# base.net
KiCad netlist of a schematic drawn in Altium Designer
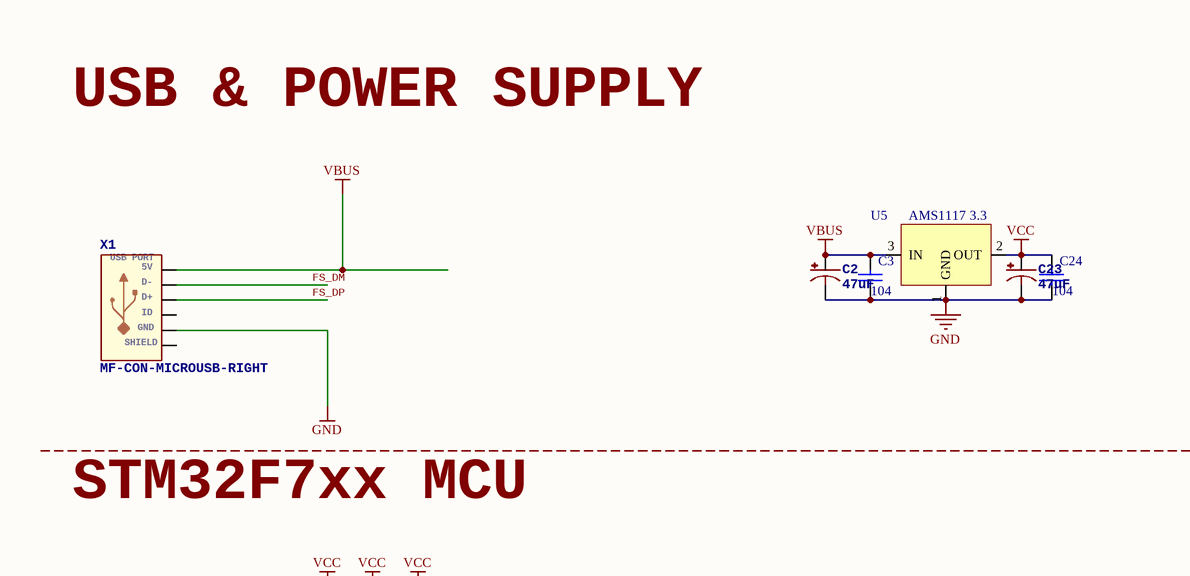
[diagram p0: base.SchDoc, top left]
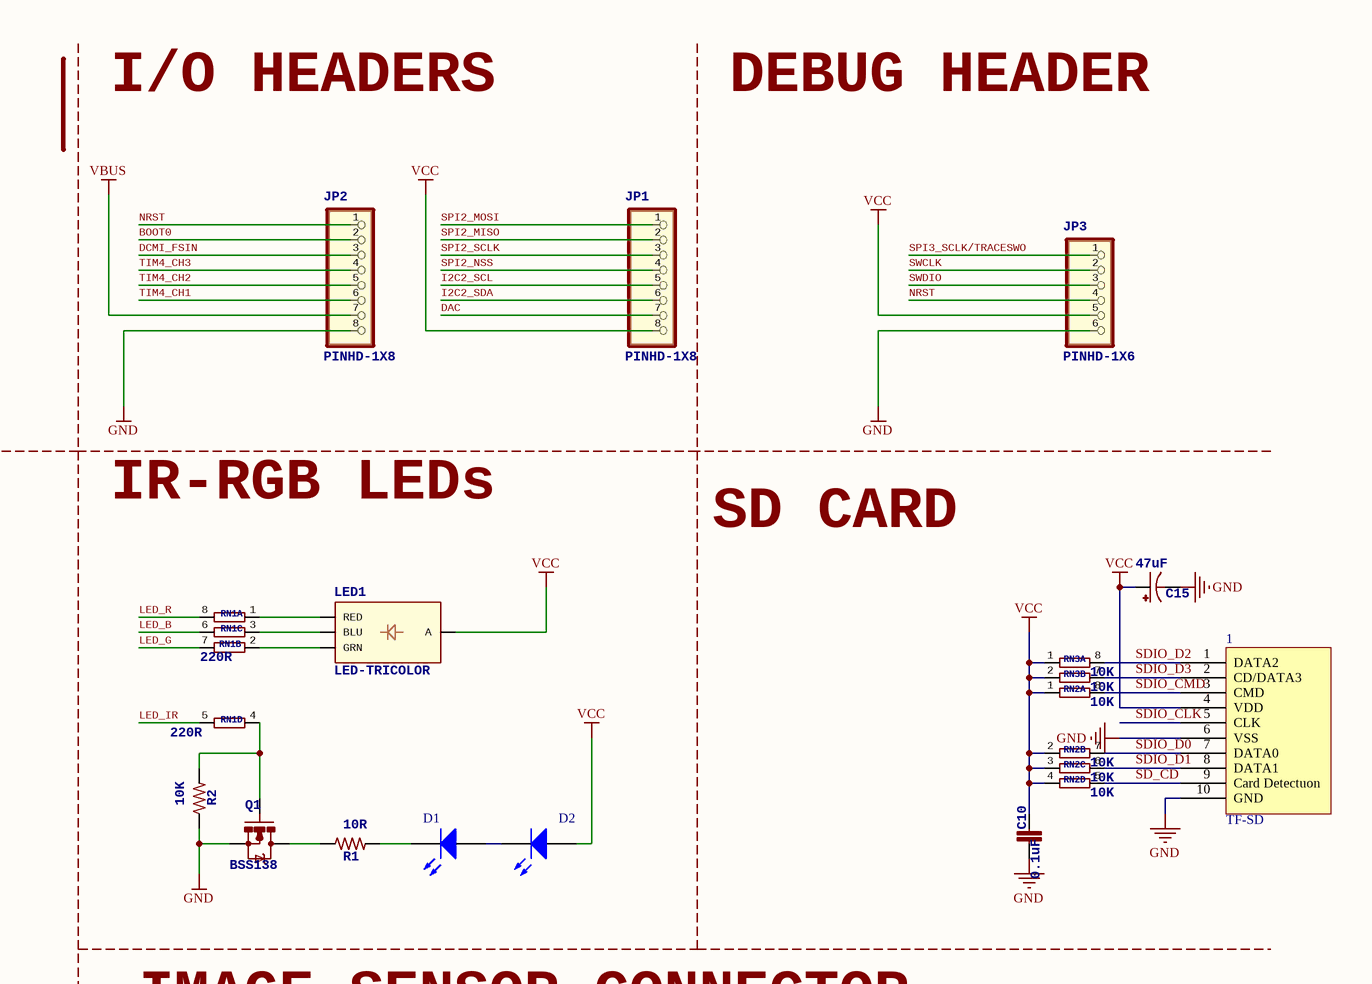
[diagram p1: base.SchDoc, top right]
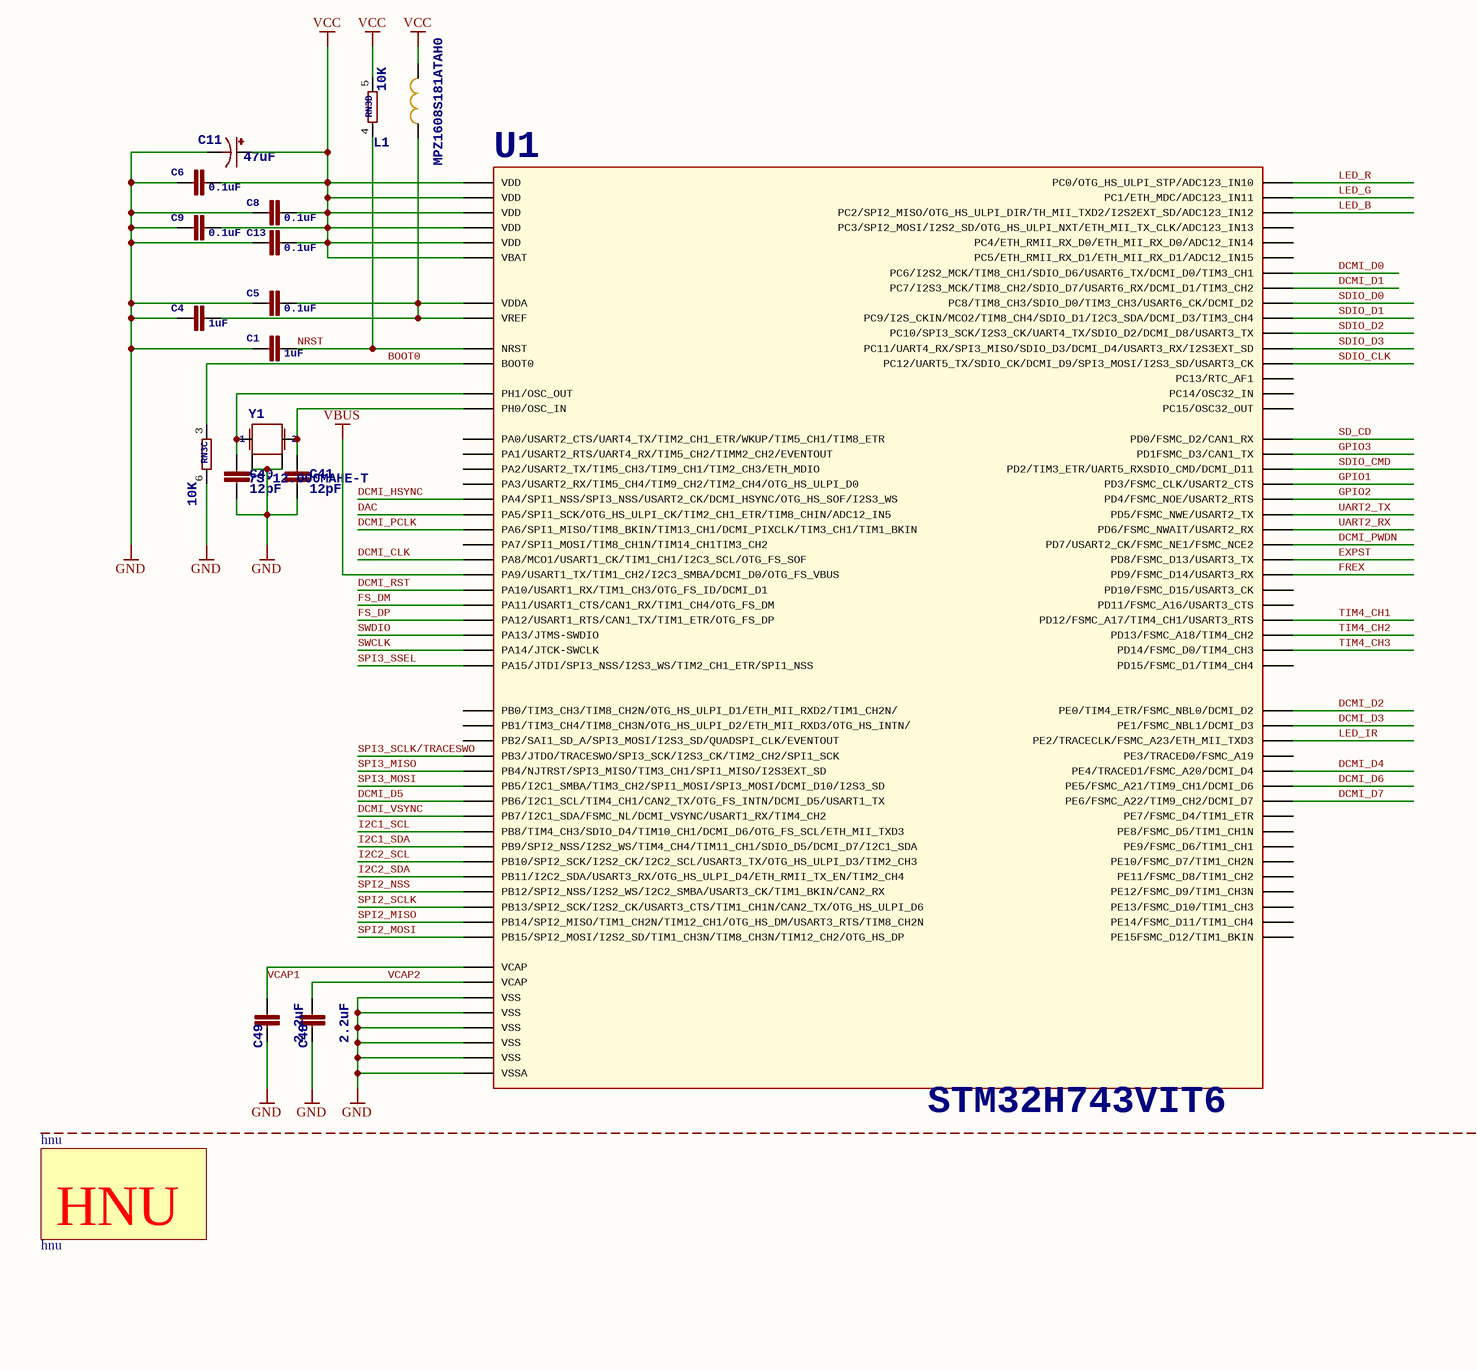
[diagram p2: base.SchDoc, bottom left]
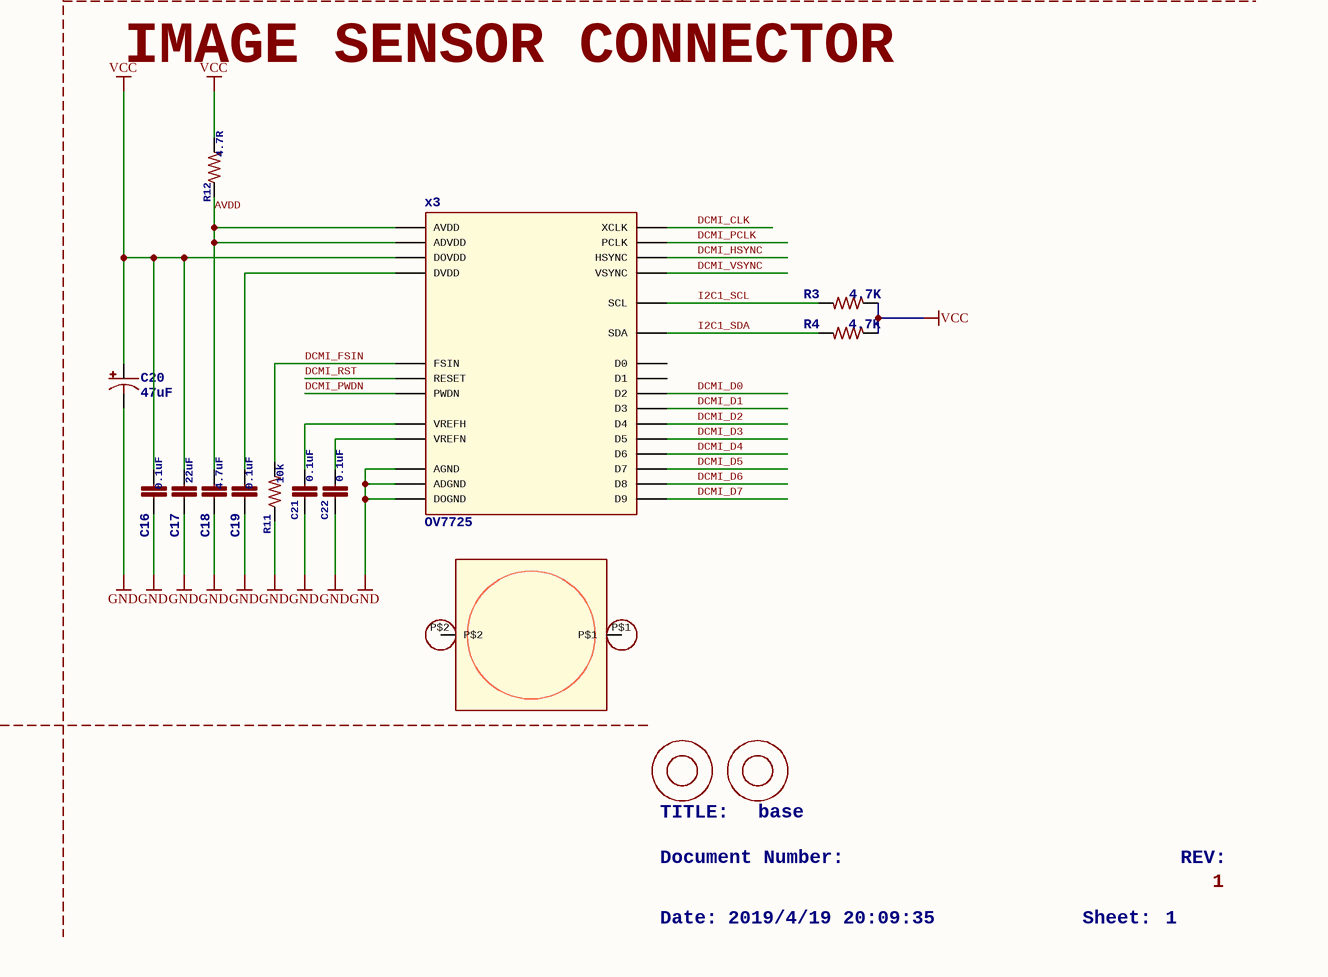
[diagram p3: base.SchDoc, bottom right]

(export (version "E")
  (design (tool "Eeschema 10.0.6"))
  (components
    (comp (ref "1") (value "TF-SD") (footprint "TF") (libsource (lib "base") (part "TF-SD")))
    (comp (ref "C1")
      (value "1uF")
      (footprint "0603-CAP")
      (description "CapacitorStandard 0603 ceramic capacitor, and 0.1\" leaded capacitor.")
      (libsource (lib "") (part "CAP0603-CAP_1"))
    )
    (comp (ref "C2") (value "47uF") (footprint "EIA3216") (libsource (lib "sfe") (part "CAP_POL1206")))
    (comp (ref "C3")
      (value "104")
      (footprint "0603-CAP")
      (description "Capacitor")
      (fields (field (name "Comment") "Cap") (field (name "PUBLISHER") "Altium Limited"))
      (libsource (lib "Miscellaneous Devices") (part "Cap"))
    )
    (comp (ref "C4")
      (value "1uF")
      (footprint "0603-CAP")
      (description "CapacitorStandard 0603 ceramic capacitor, and 0.1\" leaded capacitor.")
      (libsource (lib "") (part "CAP0603-CAP_1"))
    )
    (comp (ref "C5")
      (value "0.1uF")
      (footprint "0603-CAP")
      (description "CapacitorStandard 0603 ceramic capacitor, and 0.1\" leaded capacitor.")
      (libsource (lib "") (part "CAP0603-CAP_1"))
    )
    (comp (ref "C6")
      (value "0.1uF")
      (footprint "0603-CAP")
      (description "CapacitorStandard 0603 ceramic capacitor, and 0.1\" leaded capacitor.")
      (libsource (lib "") (part "CAP0603-CAP_1"))
    )
    (comp (ref "C8")
      (value "0.1uF")
      (footprint "0603-CAP")
      (description "CapacitorStandard 0603 ceramic capacitor, and 0.1\" leaded capacitor.")
      (libsource (lib "") (part "CAP0603-CAP_1"))
    )
    (comp (ref "C9")
      (value "0.1uF")
      (footprint "0603-CAP")
      (description "CapacitorStandard 0603 ceramic capacitor, and 0.1\" leaded capacitor.")
      (libsource (lib "") (part "CAP0603-CAP_1"))
    )
    (comp (ref "C10")
      (value "0.1uF")
      (footprint "0603-CAP")
      (description "CapacitorStandard 0603 ceramic capacitor, and 0.1\" leaded capacitor.")
      (libsource (lib "sfe") (part "CAP0603-CAP"))
    )
    (comp (ref "C11") (value "47uF") (footprint "EIA3216") (libsource (lib "") (part "CAP_POL1206_2")))
    (comp (ref "C13")
      (value "0.1uF")
      (footprint "0603-CAP")
      (description "CapacitorStandard 0603 ceramic capacitor, and 0.1\" leaded capacitor.")
      (libsource (lib "") (part "CAP0603-CAP_1"))
    )
    (comp (ref "C15") (value "47uF") (footprint "EIA3216") (libsource (lib "") (part "CAP_POL1206_1")))
    (comp (ref "C16")
      (value "0.1uF")
      (footprint "0603-CAP")
      (description "CapacitorStandard 0603 ceramic capacitor, and 0.1\" leaded capacitor.")
      (libsource (lib "") (part "CAP0603-CAP_1"))
    )
    (comp (ref "C17")
      (value "22uF")
      (footprint "0603-CAP")
      (description "CapacitorStandard 0603 ceramic capacitor, and 0.1\" leaded capacitor.")
      (libsource (lib "sfe") (part "CAP0805"))
    )
    (comp (ref "C18")
      (value "4.7uF")
      (footprint "0603-CAP")
      (description "CapacitorStandard 0603 ceramic capacitor, and 0.1\" leaded capacitor.")
      (libsource (lib "") (part "CAP0603-CAP_1"))
    )
    (comp (ref "C19")
      (value "0.1uF")
      (footprint "0603-CAP")
      (description "CapacitorStandard 0603 ceramic capacitor, and 0.1\" leaded capacitor.")
      (libsource (lib "") (part "CAP0603-CAP_1"))
    )
    (comp (ref "C20") (value "47uF") (footprint "EIA3216") (libsource (lib "sfe") (part "CAP_POL1206")))
    (comp (ref "C21")
      (value "0.1uF")
      (footprint "0603-CAP")
      (description "CapacitorStandard 0603 ceramic capacitor, and 0.1\" leaded capacitor.")
      (libsource (lib "sfe") (part "CAP0603-CAP"))
    )
    (comp (ref "C22")
      (value "0.1uF")
      (footprint "0603-CAP")
      (description "CapacitorStandard 0603 ceramic capacitor, and 0.1\" leaded capacitor.")
      (libsource (lib "sfe") (part "CAP0603-CAP"))
    )
    (comp (ref "C23") (value "47uF") (footprint "EIA3216") (libsource (lib "sfe") (part "CAP_POL1206")))
    (comp (ref "C24")
      (value "104")
      (footprint "0603-CAP")
      (description "Capacitor")
      (fields (field (name "Comment") "Cap") (field (name "PUBLISHER") "Altium Limited"))
      (libsource (lib "Miscellaneous Devices") (part "Cap"))
    )
    (comp (ref "C40")
      (value "12pF")
      (footprint "0603-CAP")
      (description "CapacitorStandard 0603 ceramic capacitor, and 0.1\" leaded capacitor.")
      (libsource (lib "") (part "CAP0603-CAP_2"))
    )
    (comp (ref "C41")
      (value "12pF")
      (footprint "0603-CAP")
      (description "CapacitorStandard 0603 ceramic capacitor, and 0.1\" leaded capacitor.")
      (libsource (lib "") (part "CAP0603-CAP_2"))
    )
    (comp (ref "C48")
      (value "2.2uF")
      (footprint "0603-CAP")
      (description "CapacitorStandard 0603 ceramic capacitor, and 0.1\" leaded capacitor.")
      (libsource (lib "sfe") (part "CAP0603-CAP"))
    )
    (comp (ref "C49")
      (value "2.2uF")
      (footprint "0603-CAP")
      (description "CapacitorStandard 0603 ceramic capacitor, and 0.1\" leaded capacitor.")
      (libsource (lib "sfe") (part "CAP0603-CAP"))
    )
    (comp (ref "D1")
      (value "LED0")
      (footprint "LED_0603")
      (description "Typical INFRARED GaAs LED")
      (fields (field (name "PUBLISHER") "Altium Limited"))
      (libsource (lib "M4(3333)") (part "LED0"))
    )
    (comp (ref "D2")
      (value "LED0")
      (footprint "LED_0603")
      (description "Typical INFRARED GaAs LED")
      (fields (field (name "PUBLISHER") "Altium Limited"))
      (libsource (lib "M4(3333)") (part "LED0"))
    )
    (comp (ref "hnu") (value "hnu") (footprint "HNU") (libsource (lib "base") (part "hnu")))
    (comp (ref "JP1")
      (value "PINHD-1X8")
      (footprint "1X08")
      (description "PIN HEADER")
      (libsource (lib "base") (part "PINHD-1X8"))
    )
    (comp (ref "JP2")
      (value "PINHD-1X8")
      (footprint "1X08")
      (description "PIN HEADER")
      (libsource (lib "base") (part "PINHD-1X8"))
    )
    (comp (ref "JP3")
      (value "PINHD-1X6")
      (footprint "1X06")
      (description "PIN HEADER")
      (libsource (lib "base") (part "PINHD-1X6"))
    )
    (comp (ref "L1")
      (value "MPZ1608S181ATAH0")
      (footprint "0603")
      (libsource (lib "base") (part "INDUCTOR0603"))
    )
    (comp (ref "LED1")
      (value "LED-TRICOLOR")
      (footprint "rgb")
      (libsource (lib "base") (part "LED-TRICOLOR"))
    )
    (comp (ref "LM1")
      (value "LENSMOUNT20MM")
      (footprint "LENSMOUNT-20MM")
      (libsource (lib "base") (part "LENSMOUNT20MM"))
    )
    (comp (ref "M1")
      (value "9774030243R")
      (footprint "2,8-PAD")
      (libsource (lib "STANDOFFS") (part "9774030151R"))
    )
    (comp (ref "M2")
      (value "9774030243R")
      (footprint "2,8-PAD")
      (libsource (lib "STANDOFFS") (part "9774030151R"))
    )
    (comp (ref "Q1")
      (value "BSS138")
      (footprint "SOT23-3")
      (libsource (lib "sfe") (part "MOSFET-NCHANNELSMD"))
    )
    (comp (ref "R1")
      (value "10R")
      (footprint "0603-RES")
      (description "ResistorBasic schematic elements and footprints for 0603, 1206, and PTH resistors.")
      (libsource (lib "sfe") (part "RESISTOR0603-RES"))
    )
    (comp (ref "R2")
      (value "10K")
      (footprint "0603-RES")
      (description "ResistorBasic schematic elements and footprints for 0603, 1206, and PTH resistors.")
      (libsource (lib "sfe") (part "RESISTOR0603-RES"))
    )
    (comp (ref "R3")
      (value "4.7K")
      (footprint "0603-RES")
      (description "ResistorBasic schematic elements and footprints for 0603, 1206, and PTH resistors.")
      (libsource (lib "sfe") (part "RESISTOR0603-RES"))
    )
    (comp (ref "R4")
      (value "4.7K")
      (footprint "0603-RES")
      (description "ResistorBasic schematic elements and footprints for 0603, 1206, and PTH resistors.")
      (libsource (lib "sfe") (part "RESISTOR0603-RES"))
    )
    (comp (ref "R11")
      (value "10k")
      (footprint "0603-RES")
      (description "ResistorBasic schematic elements and footprints for 0603, 1206, and PTH resistors.")
      (libsource (lib "sfe") (part "RESISTOR0603-RES"))
    )
    (comp (ref "R12")
      (value "4.7R")
      (footprint "0603-RES")
      (description "ResistorBasic schematic elements and footprints for 0603, 1206, and PTH resistors.")
      (libsource (lib "sfe") (part "RESISTOR0603-RES"))
    )
    (comp (ref "RN1")
      (value "220R")
      (footprint "EXBV8V")
      (description "Array Chip Resistor   Source: RS Component / Phycomp")
      (libsource (lib "resistor-dil") (part "4R-NEXBV8V"))
    )
    (comp (ref "RN2")
      (value "10K")
      (footprint "EXBV8V")
      (description "Array Chip Resistor   Source: RS Component / Phycomp")
      (libsource (lib "resistor-dil") (part "4R-NEXBV8V"))
    )
    (comp (ref "RN3")
      (value "10K")
      (footprint "EXBV8V")
      (description "Array Chip Resistor   Source: RS Component / Phycomp")
      (libsource (lib "resistor-dil") (part "4R-NEXBV8V"))
    )
    (comp (ref "U1")
      (value "STM32H743VIT6")
      (footprint "LQFP100")
      (libsource (lib "base") (part "STM32F746LQFP100"))
    )
    (comp (ref "U5") (value "AMS1117 3.3") (footprint "SOT_223") (libsource (lib "主控板载芯片") (part "AMS1117")))
    (comp (ref "X1")
      (value "MF-CON-MICROUSB-RIGHT")
      (footprint "micro_usb")
      (fields
        (field (name "USBPORT") "USB PORT")
        (field (name "5V") "5V")
        (field (name "D-") "D-")
        (field (name "D+") "D+")
        (field (name "ID") "ID")
        (field (name "GND") "GND")
        (field (name "SHIELD") "SHIELD")
      )
      (libsource (lib "base") (part "USB_MICRO_RIGHT"))
    )
    (comp (ref "x3") (value "OV7725") (footprint "CSP2-28") (libsource (lib "base") (part "OV7725")))
    (comp (ref "Y1")
      (value "7S-12.000MAHE-T")
      (footprint "CRYSTAL-2.5X2.0")
      (description "CrystalsVarious standard crystals. Proven footprints. Spark Fun Electronics SKU : COM-00534")
      (fields (field (name "1") "1") (field (name "2") "2"))
      (libsource (lib "mux") (part "CRYSTAL2.5X2.0"))
    )
  )
  (nets
    (net (code "1") (name "/AVDD") (class "Default")
      (node (ref "C18") (pin "1") (pinfunction "1_1") (pintype "passive"))
      (node (ref "R12") (pin "1") (pinfunction "1_1") (pintype "passive"))
      (node (ref "x3") (pin "A1") (pinfunction "ADVDD_A1") (pintype "power_in"))
      (node (ref "x3") (pin "B3") (pinfunction "AVDD_B3") (pintype "power_in"))
    )
    (net (code "2") (name "/BOOT0") (class "Default")
      (node (ref "JP2") (pin "2") (pinfunction "2_2") (pintype "passive"))
      (node (ref "RN3") (pin "3") (pinfunction "1_3") (pintype "passive"))
      (node (ref "U1") (pin "94") (pinfunction "BOOT0_94") (pintype "passive"))
    )
    (net (code "3") (name "/DAC") (class "Default")
      (node (ref "JP1") (pin "7") (pinfunction "7_7") (pintype "passive"))
      (node (ref "U1") (pin "29") (pinfunction "PA5/SPI1_SCK/OTG_HS_ULPI_CK/TIM2_CH1_ETR/TIM8_CHIN/ADC12_IN5_29") (pintype "passive"))
    )
    (net (code "4") (name "/DCMI_CLK") (class "Default")
      (node (ref "U1") (pin "67") (pinfunction "PA8/MCO1/USART1_CK/TIM1_CH1/I2C3_SCL/OTG_FS_SOF_67") (pintype "passive"))
      (node (ref "x3") (pin "F3") (pinfunction "XCLK_F3") (pintype "passive"))
    )
    (net (code "5") (name "/DCMI_D0") (class "Default")
      (node (ref "U1") (pin "63") (pinfunction "PC6/I2S2_MCK/TIM8_CH1/SDIO_D6/USART6_TX/DCMI_D0/TIM3_CH1_63") (pintype "passive"))
      (node (ref "x3") (pin "F5") (pinfunction "D2_F5") (pintype "passive"))
    )
    (net (code "6") (name "/DCMI_D1") (class "Default")
      (node (ref "U1") (pin "64") (pinfunction "PC7/I2S3_MCK/TIM8_CH2/SDIO_D7/USART6_RX/DCMI_D1/TIM3_CH2_64") (pintype "passive"))
      (node (ref "x3") (pin "F2") (pinfunction "D3_F2") (pintype "passive"))
    )
    (net (code "7") (name "/DCMI_D2") (class "Default")
      (node (ref "U1") (pin "97") (pinfunction "PE0/TIM4_ETR/FSMC_NBL0/DCMI_D2_97") (pintype "passive"))
      (node (ref "x3") (pin "D6") (pinfunction "D4_D6") (pintype "passive"))
    )
    (net (code "8") (name "/DCMI_D3") (class "Default")
      (node (ref "U1") (pin "98") (pinfunction "PE1/FSMC_NBL1/DCMI_D3_98") (pintype "passive"))
      (node (ref "x3") (pin "D1") (pinfunction "D5_D1") (pintype "passive"))
    )
    (net (code "9") (name "/DCMI_D4") (class "Default")
      (node (ref "U1") (pin "3") (pinfunction "PE4/TRACED1/FSMC_A20/DCMI_D4_3") (pintype "passive"))
      (node (ref "x3") (pin "E6") (pinfunction "D6_E6") (pintype "passive"))
    )
    (net (code "10") (name "/DCMI_D5") (class "Default")
      (node (ref "U1") (pin "92") (pinfunction "PB6/I2C1_SCL/TIM4_CH1/CAN2_TX/OTG_FS_INTN/DCMI_D5/USART1_TX_92") (pintype "passive"))
      (node (ref "x3") (pin "E1") (pinfunction "D7_E1") (pintype "passive"))
    )
    (net (code "11") (name "/DCMI_D6") (class "Default")
      (node (ref "U1") (pin "4") (pinfunction "PE5/FSMC_A21/TIM9_CH1/DCMI_D6_4") (pintype "passive"))
      (node (ref "x3") (pin "F6") (pinfunction "D8_F6") (pintype "passive"))
    )
    (net (code "12") (name "/DCMI_D7") (class "Default")
      (node (ref "U1") (pin "5") (pinfunction "PE6/FSMC_A22/TIM9_CH2/DCMI_D7_5") (pintype "passive"))
      (node (ref "x3") (pin "F1") (pinfunction "D9_F1") (pintype "passive"))
    )
    (net (code "13") (name "/DCMI_FSIN") (class "Default")
      (node (ref "JP2") (pin "3") (pinfunction "3_3") (pintype "passive"))
      (node (ref "R11") (pin "2") (pinfunction "2_2") (pintype "passive"))
      (node (ref "x3") (pin "A4") (pinfunction "FSIN_A4") (pintype "passive"))
    )
    (net (code "14") (name "/DCMI_HSYNC") (class "Default")
      (node (ref "U1") (pin "28") (pinfunction "PA4/SPI1_NSS/SPI3_NSS/USART2_CK/DCMI_HSYNC/OTG_HS_SOF/I2S3_WS_28") (pintype "passive"))
      (node (ref "x3") (pin "B6") (pinfunction "HSYNC_B6") (pintype "passive"))
    )
    (net (code "15") (name "/DCMI_PCLK") (class "Default")
      (node (ref "U1") (pin "30") (pinfunction "PA6/SPI1_MISO/TIM8_BKIN/TIM13_CH1/DCMI_PIXCLK/TIM3_CH1/TIM1_BKIN_30") (pintype "passive"))
      (node (ref "x3") (pin "E4") (pinfunction "PCLK_E4") (pintype "passive"))
    )
    (net (code "16") (name "/DCMI_PWDN") (class "Default")
      (node (ref "U1") (pin "88") (pinfunction "PD7/USART2_CK/FSMC_NE1/FSMC_NCE2_88") (pintype "passive"))
      (node (ref "x3") (pin "C1") (pinfunction "PWDN_C1") (pintype "passive"))
    )
    (net (code "17") (name "/DCMI_RST") (class "Default")
      (node (ref "U1") (pin "69") (pinfunction "PA10/USART1_RX/TIM1_CH3/OTG_FS_ID/DCMI_D1_69") (pintype "passive"))
      (node (ref "x3") (pin "A2") (pinfunction "RESET_A2") (pintype "passive"))
    )
    (net (code "18") (name "/DCMI_VSYNC") (class "Default")
      (node (ref "U1") (pin "93") (pinfunction "PB7/I2C1_SDA/FSMC_NL/DCMI_VSYNC/USART1_RX/TIM4_CH2_93") (pintype "passive"))
      (node (ref "x3") (pin "C6") (pinfunction "VSYNC_C6") (pintype "passive"))
    )
    (net (code "19") (name "/EXPST") (class "Default")
      (node (ref "U1") (pin "55") (pinfunction "PD8/FSMC_D13/USART3_TX_55") (pintype "passive"))
    )
    (net (code "20") (name "/FREX") (class "Default")
      (node (ref "U1") (pin "56") (pinfunction "PD9/FSMC_D14/USART3_RX_56") (pintype "passive"))
    )
    (net (code "21") (name "/FS_DM") (class "Default")
      (node (ref "U1") (pin "70") (pinfunction "PA11/USART1_CTS/CAN1_RX/TIM1_CH4/OTG_FS_DM_70") (pintype "passive"))
      (node (ref "X1") (pin "2") (pinfunction "D-_2") (pintype "passive"))
    )
    (net (code "22") (name "/FS_DP") (class "Default")
      (node (ref "U1") (pin "71") (pinfunction "PA12/USART1_RTS/CAN1_TX/TIM1_ETR/OTG_FS_DP_71") (pintype "passive"))
      (node (ref "X1") (pin "3") (pinfunction "D+_3") (pintype "passive"))
    )
    (net (code "23") (name "/GPIO1") (class "Default")
      (node (ref "U1") (pin "84") (pinfunction "PD3/FSMC_CLK/USART2_CTS_84") (pintype "passive"))
    )
    (net (code "24") (name "/GPIO2") (class "Default")
      (node (ref "U1") (pin "85") (pinfunction "PD4/FSMC_NOE/USART2_RTS_85") (pintype "passive"))
    )
    (net (code "25") (name "/GPIO3") (class "Default")
      (node (ref "U1") (pin "82") (pinfunction "PD1FSMC_D3/CAN1_TX_82") (pintype "passive"))
    )
    (net (code "26") (name "/I2C1_SCL") (class "Default")
      (node (ref "R3") (pin "2") (pinfunction "2_2") (pintype "passive"))
      (node (ref "U1") (pin "95") (pinfunction "PB8/TIM4_CH3/SDIO_D4/TIM10_CH1/DCMI_D6/OTG_FS_SCL/ETH_MII_TXD3_95") (pintype "passive"))
      (node (ref "x3") (pin "A5") (pinfunction "SCL_A5") (pintype "passive"))
    )
    (net (code "27") (name "/I2C1_SDA") (class "Default")
      (node (ref "R4") (pin "2") (pinfunction "2_2") (pintype "passive"))
      (node (ref "U1") (pin "96") (pinfunction "PB9/SPI2_NSS/I2S2_WS/TIM4_CH4/TIM11_CH1/SDIO_D5/DCMI_D7/I2C1_SDA_96") (pintype "passive"))
      (node (ref "x3") (pin "B5") (pinfunction "SDA_B5") (pintype "passive"))
    )
    (net (code "28") (name "/I2C2_SCL") (class "Default")
      (node (ref "JP1") (pin "5") (pinfunction "5_5") (pintype "passive"))
      (node (ref "U1") (pin "46") (pinfunction "PB10/SPI2_SCK/I2S2_CK/I2C2_SCL/USART3_TX/OTG_HS_ULPI_D3/TIM2_CH3_46") (pintype "passive"))
    )
    (net (code "29") (name "/I2C2_SDA") (class "Default")
      (node (ref "JP1") (pin "6") (pinfunction "6_6") (pintype "passive"))
      (node (ref "U1") (pin "47") (pinfunction "PB11/I2C2_SDA/USART3_RX/OTG_HS_ULPI_D4/ETH_RMII_TX_EN/TIM2_CH4_47") (pintype "passive"))
    )
    (net (code "30") (name "/LED_B") (class "Default")
      (node (ref "RN1") (pin "6") (pinfunction "2_6") (pintype "passive"))
      (node (ref "U1") (pin "17") (pinfunction "PC2/SPI2_MISO/OTG_HS_ULPI_DIR/TH_MII_TXD2/I2S2EXT_SD/ADC123_IN12_17") (pintype "passive"))
    )
    (net (code "31") (name "/LED_G") (class "Default")
      (node (ref "RN1") (pin "7") (pinfunction "2_7") (pintype "passive"))
      (node (ref "U1") (pin "16") (pinfunction "PC1/ETH_MDC/ADC123_IN11_16") (pintype "passive"))
    )
    (net (code "32") (name "/LED_IR") (class "Default")
      (node (ref "RN1") (pin "5") (pinfunction "2_5") (pintype "passive"))
      (node (ref "U1") (pin "1") (pinfunction "PE2/TRACECLK/FSMC_A23/ETH_MII_TXD3_1") (pintype "passive"))
    )
    (net (code "33") (name "/LED_R") (class "Default")
      (node (ref "RN1") (pin "8") (pinfunction "2_8") (pintype "passive"))
      (node (ref "U1") (pin "15") (pinfunction "PC0/OTG_HS_ULPI_STP/ADC123_IN10_15") (pintype "passive"))
    )
    (net (code "34") (name "/NRST") (class "Default")
      (node (ref "C1") (pin "1") (pinfunction "1_1") (pintype "passive"))
      (node (ref "JP2") (pin "1") (pinfunction "1_1") (pintype "passive"))
      (node (ref "JP3") (pin "4") (pinfunction "4_4") (pintype "passive"))
      (node (ref "RN3") (pin "4") (pinfunction "1_4") (pintype "passive"))
      (node (ref "U1") (pin "14") (pinfunction "NRST_14") (pintype "passive"))
    )
    (net (code "35") (name "/SDIO_CLK") (class "Default")
      (node (ref "1") (pin "5") (pinfunction "CLK_5") (pintype "passive"))
      (node (ref "U1") (pin "80") (pinfunction "PC12/UART5_TX/SDIO_CK/DCMI_D9/SPI3_MOSI/I2S3_SD/USART3_CK_80") (pintype "passive"))
    )
    (net (code "36") (name "/SDIO_CMD") (class "Default")
      (node (ref "1") (pin "3") (pinfunction "CMD_3") (pintype "passive"))
      (node (ref "RN2") (pin "8") (pinfunction "2_8") (pintype "passive"))
      (node (ref "U1") (pin "83") (pinfunction "PD2/TIM3_ETR/UART5_RXSDIO_CMD/DCMI_D11_83") (pintype "passive"))
    )
    (net (code "37") (name "/SDIO_D0") (class "Default")
      (node (ref "1") (pin "7") (pinfunction "DATA0_7") (pintype "passive"))
      (node (ref "RN2") (pin "7") (pinfunction "2_7") (pintype "passive"))
      (node (ref "U1") (pin "65") (pinfunction "PC8/TIM8_CH3/SDIO_D0/TIM3_CH3/USART6_CK/DCMI_D2_65") (pintype "passive"))
    )
    (net (code "38") (name "/SDIO_D1") (class "Default")
      (node (ref "1") (pin "8") (pinfunction "DATA1_8") (pintype "passive"))
      (node (ref "RN2") (pin "6") (pinfunction "2_6") (pintype "passive"))
      (node (ref "U1") (pin "66") (pinfunction "PC9/I2S_CKIN/MCO2/TIM8_CH4/SDIO_D1/I2C3_SDA/DCMI_D3/TIM3_CH4_66") (pintype "passive"))
    )
    (net (code "39") (name "/SDIO_D2") (class "Default")
      (node (ref "1") (pin "1") (pinfunction "DATA2_1") (pintype "passive"))
      (node (ref "RN3") (pin "8") (pinfunction "2_8") (pintype "passive"))
      (node (ref "U1") (pin "78") (pinfunction "PC10/SPI3_SCK/I2S3_CK/UART4_TX/SDIO_D2/DCMI_D8/USART3_TX_78") (pintype "passive"))
    )
    (net (code "40") (name "/SDIO_D3") (class "Default")
      (node (ref "1") (pin "2") (pinfunction "CD/DATA3_2") (pintype "passive"))
      (node (ref "RN3") (pin "7") (pinfunction "2_7") (pintype "passive"))
      (node (ref "U1") (pin "79") (pinfunction "PC11/UART4_RX/SPI3_MISO/SDIO_D3/DCMI_D4/USART3_RX/I2S3EXT_SD_79") (pintype "passive"))
    )
    (net (code "41") (name "/SD_CD") (class "Default")
      (node (ref "1") (pin "9") (pinfunction "Card_Detectuon_9") (pintype "passive"))
      (node (ref "RN2") (pin "5") (pinfunction "2_5") (pintype "passive"))
      (node (ref "U1") (pin "81") (pinfunction "PD0/FSMC_D2/CAN1_RX_81") (pintype "passive"))
    )
    (net (code "42") (name "/SPI2_MISO") (class "Default")
      (node (ref "JP1") (pin "2") (pinfunction "2_2") (pintype "passive"))
      (node (ref "U1") (pin "53") (pinfunction "PB14/SPI2_MISO/TIM1_CH2N/TIM12_CH1/OTG_HS_DM/USART3_RTS/TIM8_CH2N_53") (pintype "passive"))
    )
    (net (code "43") (name "/SPI2_MOSI") (class "Default")
      (node (ref "JP1") (pin "1") (pinfunction "1_1") (pintype "passive"))
      (node (ref "U1") (pin "54") (pinfunction "PB15/SPI2_MOSI/I2S2_SD/TIM1_CH3N/TIM8_CH3N/TIM12_CH2/OTG_HS_DP_54") (pintype "passive"))
    )
    (net (code "44") (name "/SPI2_NSS") (class "Default")
      (node (ref "JP1") (pin "4") (pinfunction "4_4") (pintype "passive"))
      (node (ref "U1") (pin "51") (pinfunction "PB12/SPI2_NSS/I2S2_WS/I2C2_SMBA/USART3_CK/TIM1_BKIN/CAN2_RX_51") (pintype "passive"))
    )
    (net (code "45") (name "/SPI2_SCLK") (class "Default")
      (node (ref "JP1") (pin "3") (pinfunction "3_3") (pintype "passive"))
      (node (ref "U1") (pin "52") (pinfunction "PB13/SPI2_SCK/I2S2_CK/USART3_CTS/TIM1_CH1N/CAN2_TX/OTG_HS_ULPI_D6_52") (pintype "passive"))
    )
    (net (code "46") (name "/SPI3_MISO") (class "Default")
      (node (ref "U1") (pin "90") (pinfunction "PB4/NJTRST/SPI3_MISO/TIM3_CH1/SPI1_MISO/I2S3EXT_SD_90") (pintype "passive"))
    )
    (net (code "47") (name "/SPI3_MOSI") (class "Default")
      (node (ref "U1") (pin "91") (pinfunction "PB5/I2C1_SMBA/TIM3_CH2/SPI1_MOSI/SPI3_MOSI/DCMI_D10/I2S3_SD_91") (pintype "passive"))
    )
    (net (code "48") (name "/SPI3_SCLK{slash}TRACESWO") (class "Default")
      (node (ref "JP3") (pin "1") (pinfunction "1_1") (pintype "passive"))
      (node (ref "U1") (pin "89") (pinfunction "PB3/JTDO/TRACESWO/SPI3_SCK/I2S3_CK/TIM2_CH2/SPI1_SCK_89") (pintype "passive"))
    )
    (net (code "49") (name "/SPI3_SSEL") (class "Default")
      (node (ref "U1") (pin "77") (pinfunction "PA15/JTDI/SPI3_NSS/I2S3_WS/TIM2_CH1_ETR/SPI1_NSS_77") (pintype "passive"))
    )
    (net (code "50") (name "/SWCLK") (class "Default")
      (node (ref "JP3") (pin "2") (pinfunction "2_2") (pintype "passive"))
      (node (ref "U1") (pin "76") (pinfunction "PA14/JTCK-SWCLK_76") (pintype "passive"))
    )
    (net (code "51") (name "/SWDIO") (class "Default")
      (node (ref "JP3") (pin "3") (pinfunction "3_3") (pintype "passive"))
      (node (ref "U1") (pin "72") (pinfunction "PA13/JTMS-SWDIO_72") (pintype "passive"))
    )
    (net (code "52") (name "/TIM4_CH1") (class "Default")
      (node (ref "JP2") (pin "6") (pinfunction "6_6") (pintype "passive"))
      (node (ref "U1") (pin "59") (pinfunction "PD12/FSMC_A17/TIM4_CH1/USART3_RTS_59") (pintype "passive"))
    )
    (net (code "53") (name "/TIM4_CH2") (class "Default")
      (node (ref "JP2") (pin "5") (pinfunction "5_5") (pintype "passive"))
      (node (ref "U1") (pin "60") (pinfunction "PD13/FSMC_A18/TIM4_CH2_60") (pintype "passive"))
    )
    (net (code "54") (name "/TIM4_CH3") (class "Default")
      (node (ref "JP2") (pin "4") (pinfunction "4_4") (pintype "passive"))
      (node (ref "U1") (pin "61") (pinfunction "PD14/FSMC_D0/TIM4_CH3_61") (pintype "passive"))
    )
    (net (code "55") (name "/UART2_RX") (class "Default")
      (node (ref "U1") (pin "87") (pinfunction "PD6/FSMC_NWAIT/USART2_RX_87") (pintype "passive"))
    )
    (net (code "56") (name "/UART2_TX") (class "Default")
      (node (ref "U1") (pin "86") (pinfunction "PD5/FSMC_NWE/USART2_TX_86") (pintype "passive"))
    )
    (net (code "57") (name "/VCAP1") (class "Default")
      (node (ref "C49") (pin "1") (pinfunction "1_1") (pintype "passive"))
      (node (ref "U1") (pin "48") (pinfunction "VCAP_48") (pintype "power_in"))
    )
    (net (code "58") (name "/VCAP2") (class "Default")
      (node (ref "C48") (pin "1") (pinfunction "1_1") (pintype "passive"))
      (node (ref "U1") (pin "73") (pinfunction "VCAP_73") (pintype "power_in"))
    )
    (net (code "59") (name "GND") (class "Default")
      (node (ref "1") (pin "10") (pinfunction "GND_10") (pintype "passive"))
      (node (ref "1") (pin "6") (pinfunction "VSS_6") (pintype "passive"))
      (node (ref "C1") (pin "2") (pinfunction "2_2") (pintype "passive"))
      (node (ref "C10") (pin "2") (pinfunction "2_2") (pintype "passive"))
      (node (ref "C11") (pin "C") (pinfunction "-_C") (pintype "passive"))
      (node (ref "C13") (pin "2") (pinfunction "2_2") (pintype "passive"))
      (node (ref "C15") (pin "C") (pinfunction "-_C") (pintype "passive"))
      (node (ref "C16") (pin "2") (pinfunction "2_2") (pintype "passive"))
      (node (ref "C17") (pin "2") (pinfunction "2_2") (pintype "passive"))
      (node (ref "C18") (pin "2") (pinfunction "2_2") (pintype "passive"))
      (node (ref "C19") (pin "2") (pinfunction "2_2") (pintype "passive"))
      (node (ref "C2") (pin "C") (pinfunction "-_C") (pintype "passive"))
      (node (ref "C20") (pin "C") (pinfunction "-_C") (pintype "passive"))
      (node (ref "C21") (pin "2") (pinfunction "2_2") (pintype "passive"))
      (node (ref "C22") (pin "2") (pinfunction "2_2") (pintype "passive"))
      (node (ref "C23") (pin "C") (pinfunction "-_C") (pintype "passive"))
      (node (ref "C24") (pin "2") (pinfunction "2_2") (pintype "passive"))
      (node (ref "C3") (pin "2") (pinfunction "2_2") (pintype "passive"))
      (node (ref "C4") (pin "2") (pinfunction "2_2") (pintype "passive"))
      (node (ref "C40") (pin "1") (pinfunction "1_1") (pintype "passive"))
      (node (ref "C41") (pin "1") (pinfunction "1_1") (pintype "passive"))
      (node (ref "C48") (pin "2") (pinfunction "2_2") (pintype "passive"))
      (node (ref "C49") (pin "2") (pinfunction "2_2") (pintype "passive"))
      (node (ref "C5") (pin "2") (pinfunction "2_2") (pintype "passive"))
      (node (ref "C6") (pin "2") (pinfunction "2_2") (pintype "passive"))
      (node (ref "C8") (pin "2") (pinfunction "2_2") (pintype "passive"))
      (node (ref "C9") (pin "2") (pinfunction "2_2") (pintype "passive"))
      (node (ref "JP2") (pin "8") (pinfunction "8_8") (pintype "passive"))
      (node (ref "JP3") (pin "6") (pinfunction "6_6") (pintype "passive"))
      (node (ref "Q1") (pin "2") (pinfunction "S_2") (pintype "passive"))
      (node (ref "R11") (pin "1") (pinfunction "1_1") (pintype "passive"))
      (node (ref "R2") (pin "1") (pinfunction "1_1") (pintype "passive"))
      (node (ref "RN3") (pin "6") (pinfunction "2_6") (pintype "passive"))
      (node (ref "U1") (pin "10") (pinfunction "VSS_10") (pintype "power_in"))
      (node (ref "U1") (pin "19") (pinfunction "VSSA_19") (pintype "power_in"))
      (node (ref "U1") (pin "26") (pinfunction "VSS_26") (pintype "power_in"))
      (node (ref "U1") (pin "49") (pinfunction "VSS_49") (pintype "power_in"))
      (node (ref "U1") (pin "74") (pinfunction "VSS_74") (pintype "power_in"))
      (node (ref "U1") (pin "99") (pinfunction "VSS_99") (pintype "power_in"))
      (node (ref "U5") (pin "1") (pinfunction "GND_1") (pintype "passive"))
      (node (ref "X1") (pin "5") (pinfunction "GND_5") (pintype "power_in"))
      (node (ref "Y1") (pin "2") (pinfunction "P$1_2") (pintype "open_emitter"))
      (node (ref "Y1") (pin "4") (pinfunction "P$2_4") (pintype "open_emitter"))
      (node (ref "x3") (pin "B1") (pinfunction "ADGND_B1") (pintype "power_in"))
      (node (ref "x3") (pin "B4") (pinfunction "AGND_B4") (pintype "power_in"))
      (node (ref "x3") (pin "F4") (pinfunction "DOGND_F4") (pintype "power_in"))
    )
    (net (code "60") (name "Net-(D1-A)") (class "Default")
      (node (ref "D1") (pin "1") (pinfunction "A_1") (pintype "passive"))
      (node (ref "D2") (pin "2") (pinfunction "K_2") (pintype "passive"))
    )
    (net (code "61") (name "Net-(D1-K)") (class "Default")
      (node (ref "D1") (pin "2") (pinfunction "K_2") (pintype "passive"))
      (node (ref "R1") (pin "2") (pinfunction "2_2") (pintype "passive"))
    )
    (net (code "62") (name "Net-(LED1-BLU)") (class "Default")
      (node (ref "LED1") (pin "B") (pinfunction "BLU_B") (pintype "passive"))
      (node (ref "RN1") (pin "3") (pinfunction "1_3") (pintype "passive"))
    )
    (net (code "63") (name "Net-(LED1-GRN)") (class "Default")
      (node (ref "LED1") (pin "G") (pinfunction "GRN_G") (pintype "passive"))
      (node (ref "RN1") (pin "2") (pinfunction "1_2") (pintype "passive"))
    )
    (net (code "64") (name "Net-(LED1-RED)") (class "Default")
      (node (ref "LED1") (pin "R") (pinfunction "RED_R") (pintype "passive"))
      (node (ref "RN1") (pin "1") (pinfunction "1_1") (pintype "passive"))
    )
    (net (code "65") (name "Net-(Q1-D)") (class "Default")
      (node (ref "Q1") (pin "3") (pinfunction "D_3") (pintype "passive"))
      (node (ref "R1") (pin "1") (pinfunction "1_1") (pintype "passive"))
    )
    (net (code "66") (name "Net-(Q1-G)") (class "Default")
      (node (ref "Q1") (pin "1") (pinfunction "G_1") (pintype "passive"))
      (node (ref "R2") (pin "2") (pinfunction "2_2") (pintype "passive"))
      (node (ref "RN1") (pin "4") (pinfunction "1_4") (pintype "passive"))
    )
    (net (code "67") (name "Net-(U1-PH0{slash}OSC_IN)") (class "Default")
      (node (ref "C41") (pin "2") (pinfunction "2_2") (pintype "passive"))
      (node (ref "U1") (pin "12") (pinfunction "PH0/OSC_IN_12") (pintype "passive"))
      (node (ref "Y1") (pin "1") (pinfunction "1_1") (pintype "passive"))
    )
    (net (code "68") (name "Net-(U1-PH1{slash}OSC_OUT)") (class "Default")
      (node (ref "C40") (pin "2") (pinfunction "2_2") (pintype "passive"))
      (node (ref "U1") (pin "13") (pinfunction "PH1/OSC_OUT_13") (pintype "passive"))
      (node (ref "Y1") (pin "3") (pinfunction "2_3") (pintype "passive"))
    )
    (net (code "69") (name "Net-(U1-VDDA)") (class "Default")
      (node (ref "C4") (pin "1") (pinfunction "1_1") (pintype "passive"))
      (node (ref "C5") (pin "1") (pinfunction "1_1") (pintype "passive"))
      (node (ref "L1") (pin "1") (pinfunction "1_1") (pintype "passive"))
      (node (ref "U1") (pin "20") (pinfunction "VREF_20") (pintype "power_in"))
      (node (ref "U1") (pin "21") (pinfunction "VDDA_21") (pintype "power_in"))
    )
    (net (code "70") (name "Net-(x3-DVDD)") (class "Default")
      (node (ref "C19") (pin "1") (pinfunction "1_1") (pintype "passive"))
      (node (ref "x3") (pin "E3") (pinfunction "DVDD_E3") (pintype "power_in"))
    )
    (net (code "71") (name "Net-(x3-VREFH)") (class "Default")
      (node (ref "C21") (pin "1") (pinfunction "1_1") (pintype "passive"))
      (node (ref "x3") (pin "A3") (pinfunction "VREFH_A3") (pintype "power_in"))
    )
    (net (code "72") (name "Net-(x3-VREFN)") (class "Default")
      (node (ref "C22") (pin "1") (pinfunction "1_1") (pintype "passive"))
      (node (ref "x3") (pin "B2") (pinfunction "VREFN_B2") (pintype "power_in"))
    )
    (net (code "73") (name "VBUS") (class "Default")
      (node (ref "C2") (pin "A") (pinfunction "+_A") (pintype "passive"))
      (node (ref "C3") (pin "1") (pinfunction "1_1") (pintype "passive"))
      (node (ref "JP2") (pin "7") (pinfunction "7_7") (pintype "passive"))
      (node (ref "U1") (pin "68") (pinfunction "PA9/USART1_TX/TIM1_CH2/I2C3_SMBA/DCMI_D0/OTG_FS_VBUS_68") (pintype "passive"))
      (node (ref "U5") (pin "3") (pinfunction "IN_3") (pintype "passive"))
      (node (ref "X1") (pin "1") (pinfunction "5V_1") (pintype "power_in"))
    )
    (net (code "74") (name "VCC") (class "Default")
      (node (ref "1") (pin "4") (pinfunction "VDD_4") (pintype "passive"))
      (node (ref "C10") (pin "1") (pinfunction "1_1") (pintype "passive"))
      (node (ref "C11") (pin "A") (pinfunction "+_A") (pintype "passive"))
      (node (ref "C13") (pin "1") (pinfunction "1_1") (pintype "passive"))
      (node (ref "C15") (pin "A") (pinfunction "+_A") (pintype "passive"))
      (node (ref "C16") (pin "1") (pinfunction "1_1") (pintype "passive"))
      (node (ref "C17") (pin "1") (pinfunction "1_1") (pintype "passive"))
      (node (ref "C20") (pin "A") (pinfunction "+_A") (pintype "passive"))
      (node (ref "C23") (pin "A") (pinfunction "+_A") (pintype "passive"))
      (node (ref "C24") (pin "1") (pinfunction "1_1") (pintype "passive"))
      (node (ref "C6") (pin "1") (pinfunction "1_1") (pintype "passive"))
      (node (ref "C8") (pin "1") (pinfunction "1_1") (pintype "passive"))
      (node (ref "C9") (pin "1") (pinfunction "1_1") (pintype "passive"))
      (node (ref "D2") (pin "1") (pinfunction "A_1") (pintype "passive"))
      (node (ref "JP1") (pin "8") (pinfunction "8_8") (pintype "passive"))
      (node (ref "JP3") (pin "5") (pinfunction "5_5") (pintype "passive"))
      (node (ref "L1") (pin "2") (pinfunction "2_2") (pintype "passive"))
      (node (ref "LED1") (pin "A") (pinfunction "A_A") (pintype "passive"))
      (node (ref "R12") (pin "2") (pinfunction "2_2") (pintype "passive"))
      (node (ref "R3") (pin "1") (pinfunction "1_1") (pintype "passive"))
      (node (ref "R4") (pin "1") (pinfunction "1_1") (pintype "passive"))
      (node (ref "RN2") (pin "1") (pinfunction "1_1") (pintype "passive"))
      (node (ref "RN2") (pin "2") (pinfunction "1_2") (pintype "passive"))
      (node (ref "RN2") (pin "3") (pinfunction "1_3") (pintype "passive"))
      (node (ref "RN2") (pin "4") (pinfunction "1_4") (pintype "passive"))
      (node (ref "RN3") (pin "1") (pinfunction "1_1") (pintype "passive"))
      (node (ref "RN3") (pin "2") (pinfunction "1_2") (pintype "passive"))
      (node (ref "RN3") (pin "5") (pinfunction "2_5") (pintype "passive"))
      (node (ref "U1") (pin "100") (pinfunction "VDD_100") (pintype "power_in"))
      (node (ref "U1") (pin "11") (pinfunction "VDD_11") (pintype "power_in"))
      (node (ref "U1") (pin "27") (pinfunction "VDD_27") (pintype "power_in"))
      (node (ref "U1") (pin "50") (pinfunction "VDD_50") (pintype "power_in"))
      (node (ref "U1") (pin "6") (pinfunction "VBAT_6") (pintype "power_in"))
      (node (ref "U1") (pin "75") (pinfunction "VDD_75") (pintype "power_in"))
      (node (ref "U5") (pin "2") (pinfunction "OUT_2") (pintype "passive"))
      (node (ref "x3") (pin "E5") (pinfunction "DOVDD_E5") (pintype "power_in"))
    )
    (net (code "75") (name "unconnected-(LM1-PadP$1)") (class "Default")
      (node (ref "LM1") (pin "P$1") (pinfunction "P$1_P$1") (pintype "open_emitter"))
    )
    (net (code "76") (name "unconnected-(LM1-PadP$2)") (class "Default")
      (node (ref "LM1") (pin "P$2") (pinfunction "P$2_P$2") (pintype "open_emitter"))
    )
    (net (code "77") (name "unconnected-(U1-PA0{slash}USART2_CTS{slash}UART4_TX{slash}TIM2_CH1_ETR{slash}WKUP{slash}TIM5_CH1{slash}TIM8_ETR-Pad22)") (class "Default")
      (node (ref "U1") (pin "22") (pinfunction "PA0/USART2_CTS/UART4_TX/TIM2_CH1_ETR/WKUP/TIM5_CH1/TIM8_ETR_22") (pintype "passive"))
    )
    (net (code "78") (name "unconnected-(U1-PA1{slash}USART2_RTS{slash}UART4_RX{slash}TIM5_CH2{slash}TIMM2_CH2{slash}EVENTOUT-Pad23)") (class "Default")
      (node (ref "U1") (pin "23") (pinfunction "PA1/USART2_RTS/UART4_RX/TIM5_CH2/TIMM2_CH2/EVENTOUT_23") (pintype "passive"))
    )
    (net (code "79") (name "unconnected-(U1-PA2{slash}USART2_TX{slash}TIM5_CH3{slash}TIM9_CH1{slash}TIM2_CH3{slash}ETH_MDIO-Pad24)") (class "Default")
      (node (ref "U1") (pin "24") (pinfunction "PA2/USART2_TX/TIM5_CH3/TIM9_CH1/TIM2_CH3/ETH_MDIO_24") (pintype "passive"))
    )
    (net (code "80") (name "unconnected-(U1-PA3{slash}USART2_RX{slash}TIM5_CH4{slash}TIM9_CH2{slash}TIM2_CH4{slash}OTG_HS_ULPI_D0-Pad25)") (class "Default")
      (node (ref "U1") (pin "25") (pinfunction "PA3/USART2_RX/TIM5_CH4/TIM9_CH2/TIM2_CH4/OTG_HS_ULPI_D0_25") (pintype "passive"))
    )
    (net (code "81") (name "unconnected-(U1-PA7{slash}SPI1_MOSI{slash}TIM8_CH1N{slash}TIM14_CH1TIM3_CH2-Pad31)") (class "Default")
      (node (ref "U1") (pin "31") (pinfunction "PA7/SPI1_MOSI/TIM8_CH1N/TIM14_CH1TIM3_CH2_31") (pintype "passive"))
    )
    (net (code "82") (name "unconnected-(U1-PB0{slash}TIM3_CH3{slash}TIM8_CH2N{slash}OTG_HS_ULPI_D1{slash}ETH_MII_RXD2{slash}TIM1_CH2N{slash}-Pad34)") (class "Default")
      (node (ref "U1") (pin "34") (pinfunction "PB0/TIM3_CH3/TIM8_CH2N/OTG_HS_ULPI_D1/ETH_MII_RXD2/TIM1_CH2N/_34") (pintype "passive"))
    )
    (net (code "83") (name "unconnected-(U1-PB1{slash}TIM3_CH4{slash}TIM8_CH3N{slash}OTG_HS_ULPI_D2{slash}ETH_MII_RXD3{slash}OTG_HS_INTN{slash}-Pad35)") (class "Default")
      (node (ref "U1") (pin "35") (pinfunction "PB1/TIM3_CH4/TIM8_CH3N/OTG_HS_ULPI_D2/ETH_MII_RXD3/OTG_HS_INTN/_35") (pintype "passive"))
    )
    (net (code "84") (name "unconnected-(U1-PB2{slash}SAI1_SD_A{slash}SPI3_MOSI{slash}I2S3_SD{slash}QUADSPI_CLK{slash}EVENTOUT-Pad36)") (class "Default")
      (node (ref "U1") (pin "36") (pinfunction "PB2/SAI1_SD_A/SPI3_MOSI/I2S3_SD/QUADSPI_CLK/EVENTOUT_36") (pintype "passive"))
    )
    (net (code "85") (name "unconnected-(U1-PC3{slash}SPI2_MOSI{slash}I2S2_SD{slash}OTG_HS_ULPI_NXT{slash}ETH_MII_TX_CLK{slash}ADC123_IN13-Pad18)") (class "Default")
      (node (ref "U1") (pin "18") (pinfunction "PC3/SPI2_MOSI/I2S2_SD/OTG_HS_ULPI_NXT/ETH_MII_TX_CLK/ADC123_IN13_18") (pintype "passive"))
    )
    (net (code "86") (name "unconnected-(U1-PC4{slash}ETH_RMII_RX_D0{slash}ETH_MII_RX_D0{slash}ADC12_IN14-Pad32)") (class "Default")
      (node (ref "U1") (pin "32") (pinfunction "PC4/ETH_RMII_RX_D0/ETH_MII_RX_D0/ADC12_IN14_32") (pintype "passive"))
    )
    (net (code "87") (name "unconnected-(U1-PC5{slash}ETH_RMII_RX_D1{slash}ETH_MII_RX_D1{slash}ADC12_IN15-Pad33)") (class "Default")
      (node (ref "U1") (pin "33") (pinfunction "PC5/ETH_RMII_RX_D1/ETH_MII_RX_D1/ADC12_IN15_33") (pintype "passive"))
    )
    (net (code "88") (name "unconnected-(U1-PC13{slash}RTC_AF1-Pad7)") (class "Default")
      (node (ref "U1") (pin "7") (pinfunction "PC13/RTC_AF1_7") (pintype "passive"))
    )
    (net (code "89") (name "unconnected-(U1-PC14{slash}OSC32_IN-Pad8)") (class "Default")
      (node (ref "U1") (pin "8") (pinfunction "PC14/OSC32_IN_8") (pintype "passive"))
    )
    (net (code "90") (name "unconnected-(U1-PC15{slash}OSC32_OUT-Pad9)") (class "Default")
      (node (ref "U1") (pin "9") (pinfunction "PC15/OSC32_OUT_9") (pintype "passive"))
    )
    (net (code "91") (name "unconnected-(U1-PD10{slash}FSMC_D15{slash}USART3_CK-Pad57)") (class "Default")
      (node (ref "U1") (pin "57") (pinfunction "PD10/FSMC_D15/USART3_CK_57") (pintype "passive"))
    )
    (net (code "92") (name "unconnected-(U1-PD11{slash}FSMC_A16{slash}USART3_CTS-Pad58)") (class "Default")
      (node (ref "U1") (pin "58") (pinfunction "PD11/FSMC_A16/USART3_CTS_58") (pintype "passive"))
    )
    (net (code "93") (name "unconnected-(U1-PD15{slash}FSMC_D1{slash}TIM4_CH4-Pad62)") (class "Default")
      (node (ref "U1") (pin "62") (pinfunction "PD15/FSMC_D1/TIM4_CH4_62") (pintype "passive"))
    )
    (net (code "94") (name "unconnected-(U1-PE3{slash}TRACED0{slash}FSMC_A19-Pad2)") (class "Default")
      (node (ref "U1") (pin "2") (pinfunction "PE3/TRACED0/FSMC_A19_2") (pintype "passive"))
    )
    (net (code "95") (name "unconnected-(U1-PE7{slash}FSMC_D4{slash}TIM1_ETR-Pad37)") (class "Default")
      (node (ref "U1") (pin "37") (pinfunction "PE7/FSMC_D4/TIM1_ETR_37") (pintype "passive"))
    )
    (net (code "96") (name "unconnected-(U1-PE8{slash}FSMC_D5{slash}TIM1_CH1N-Pad38)") (class "Default")
      (node (ref "U1") (pin "38") (pinfunction "PE8/FSMC_D5/TIM1_CH1N_38") (pintype "passive"))
    )
    (net (code "97") (name "unconnected-(U1-PE9{slash}FSMC_D6{slash}TIM1_CH1-Pad39)") (class "Default")
      (node (ref "U1") (pin "39") (pinfunction "PE9/FSMC_D6/TIM1_CH1_39") (pintype "passive"))
    )
    (net (code "98") (name "unconnected-(U1-PE10{slash}FSMC_D7{slash}TIM1_CH2N-Pad40)") (class "Default")
      (node (ref "U1") (pin "40") (pinfunction "PE10/FSMC_D7/TIM1_CH2N_40") (pintype "passive"))
    )
    (net (code "99") (name "unconnected-(U1-PE11{slash}FSMC_D8{slash}TIM1_CH2-Pad41)") (class "Default")
      (node (ref "U1") (pin "41") (pinfunction "PE11/FSMC_D8/TIM1_CH2_41") (pintype "passive"))
    )
    (net (code "100") (name "unconnected-(U1-PE12{slash}FSMC_D9{slash}TIM1_CH3N-Pad42)") (class "Default")
      (node (ref "U1") (pin "42") (pinfunction "PE12/FSMC_D9/TIM1_CH3N_42") (pintype "passive"))
    )
    (net (code "101") (name "unconnected-(U1-PE13{slash}FSMC_D10{slash}TIM1_CH3-Pad43)") (class "Default")
      (node (ref "U1") (pin "43") (pinfunction "PE13/FSMC_D10/TIM1_CH3_43") (pintype "passive"))
    )
    (net (code "102") (name "unconnected-(U1-PE14{slash}FSMC_D11{slash}TIM1_CH4-Pad44)") (class "Default")
      (node (ref "U1") (pin "44") (pinfunction "PE14/FSMC_D11/TIM1_CH4_44") (pintype "passive"))
    )
    (net (code "103") (name "unconnected-(U1-PE15FSMC_D12{slash}TIM1_BKIN-Pad45)") (class "Default")
      (node (ref "U1") (pin "45") (pinfunction "PE15FSMC_D12/TIM1_BKIN_45") (pintype "passive"))
    )
    (net (code "104") (name "unconnected-(X1-ID-Pad4)") (class "Default")
      (node (ref "X1") (pin "4") (pinfunction "ID_4") (pintype "passive"))
    )
    (net (code "105") (name "unconnected-(X1-SLD-PadS1_S2_S3_S4_S5_S6)") (class "Default")
      (node (ref "X1") (pin "S1_S2_S3_S4_S5_S6") (pinfunction "SLD_S1_S2_S3_S4_S5_S6") (pintype "passive"))
    )
    (net (code "106") (name "unconnected-(x3-D0-PadA6)") (class "Default")
      (node (ref "x3") (pin "A6") (pinfunction "D0_A6") (pintype "passive"))
    )
    (net (code "107") (name "unconnected-(x3-D1-PadE2)") (class "Default")
      (node (ref "x3") (pin "E2") (pinfunction "D1_E2") (pintype "passive"))
    )
  )
)
